# W5500_1_12.net
KiCad netlist of a schematic drawn in Altium Designer
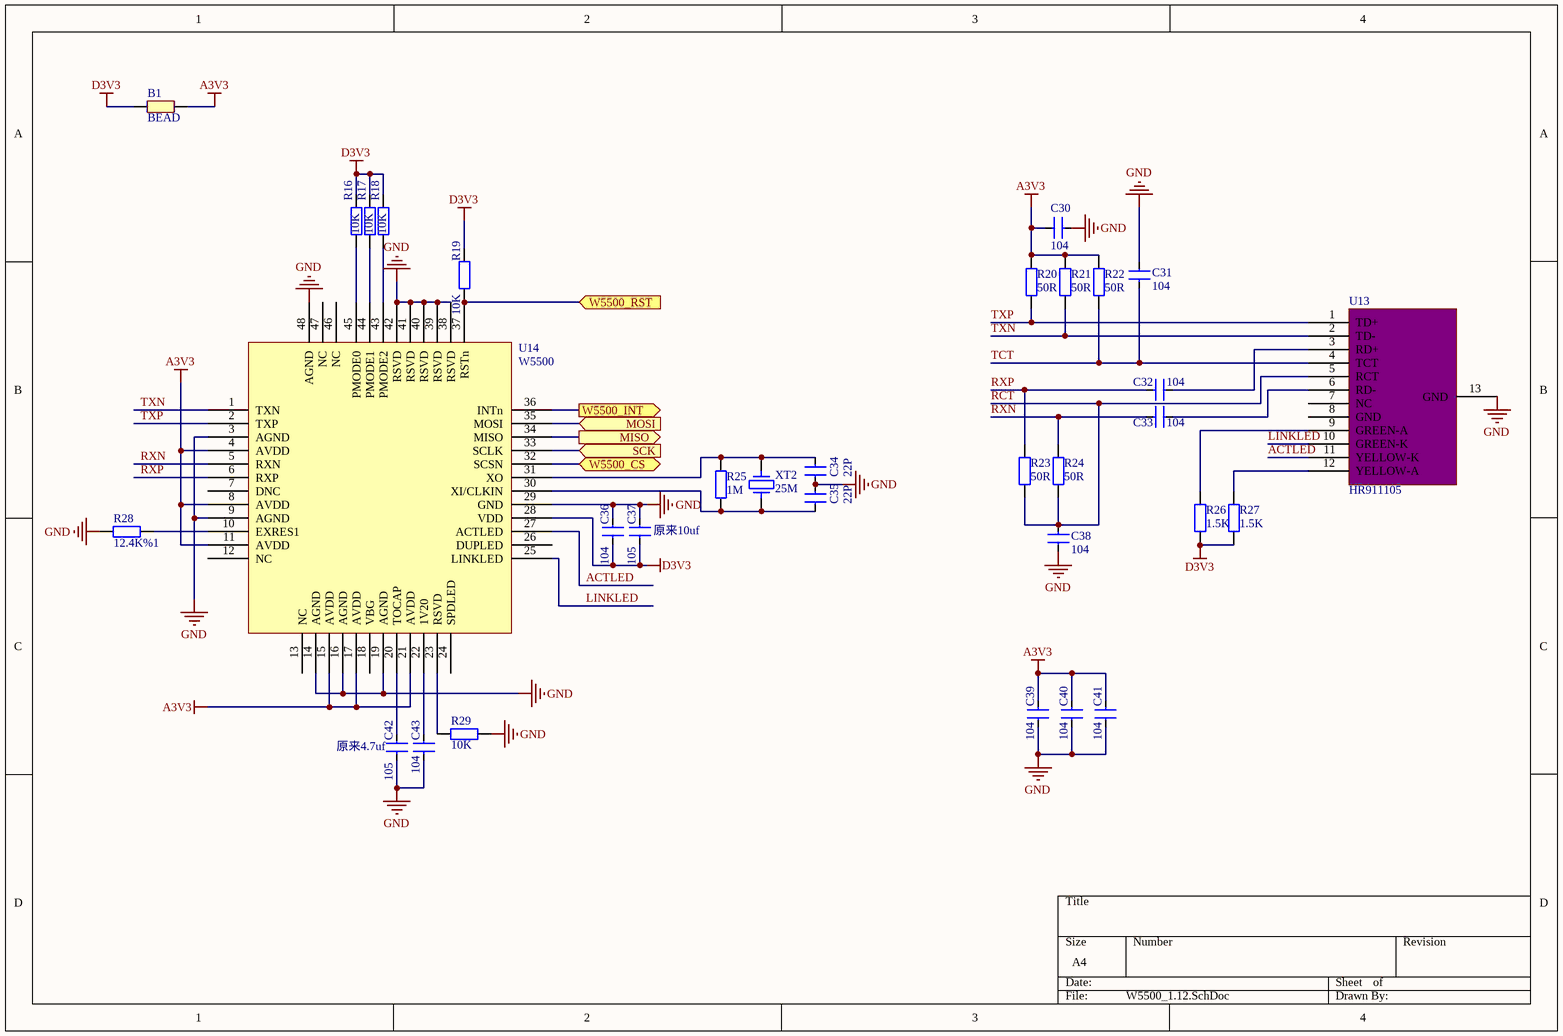
[diagram p0: W5500_1.12.SchDoc]

(export (version "E")
  (design (tool "Eeschema 10.0.6"))
  (components
    (comp (ref "B1")
      (value "BEAD")
      (footprint "0603L")
      (description "磁珠")
      (libsource (lib "lib_AD") (part "BEAD"))
    )
    (comp (ref "C30")
      (value "104")
      (footprint "0603C")
      (description "普通小电容")
      (libsource (lib "lib_AD") (part "CAP"))
    )
    (comp (ref "C31")
      (value "104")
      (footprint "0603C")
      (description "普通小电容")
      (libsource (lib "lib_AD") (part "CAP"))
    )
    (comp (ref "C32")
      (value "104")
      (footprint "0603C")
      (description "普通小电容")
      (libsource (lib "lib_AD") (part "CAP"))
    )
    (comp (ref "C33")
      (value "104")
      (footprint "0603C")
      (description "普通小电容")
      (libsource (lib "lib_AD") (part "CAP"))
    )
    (comp (ref "C34")
      (value "22P")
      (footprint "0603C")
      (description "普通小电容")
      (libsource (lib "lib_AD") (part "CAP"))
    )
    (comp (ref "C35")
      (value "22P")
      (footprint "0603C")
      (description "普通小电容")
      (libsource (lib "lib_AD") (part "CAP"))
    )
    (comp (ref "C36")
      (value "104")
      (footprint "0603C")
      (description "普通小电容")
      (libsource (lib "lib_AD") (part "CAP"))
    )
    (comp (ref "C37")
      (value "105")
      (footprint "0603C")
      (description "普通小电容")
      (libsource (lib "lib_AD") (part "CAP"))
    )
    (comp (ref "C38")
      (value "104")
      (footprint "0603C")
      (description "普通小电容")
      (libsource (lib "lib_AD") (part "CAP"))
    )
    (comp (ref "C39")
      (value "104")
      (footprint "0603C")
      (description "普通小电容")
      (libsource (lib "lib_AD") (part "CAP"))
    )
    (comp (ref "C40")
      (value "104")
      (footprint "0603C")
      (description "普通小电容")
      (libsource (lib "lib_AD") (part "CAP"))
    )
    (comp (ref "C41")
      (value "104")
      (footprint "0603C")
      (description "普通小电容")
      (libsource (lib "lib_AD") (part "CAP"))
    )
    (comp (ref "C42")
      (value "105")
      (footprint "0603C")
      (description "普通小电容")
      (libsource (lib "lib_AD") (part "CAP"))
    )
    (comp (ref "C43")
      (value "104")
      (footprint "0603C")
      (description "普通小电容")
      (libsource (lib "lib_AD") (part "CAP"))
    )
    (comp (ref "R16")
      (value "10K")
      (footprint "0603R")
      (description "普通电阻")
      (libsource (lib "lib_AD") (part "RES"))
    )
    (comp (ref "R17")
      (value "10K")
      (footprint "0603R")
      (description "普通电阻")
      (libsource (lib "lib_AD") (part "RES"))
    )
    (comp (ref "R18")
      (value "10K")
      (footprint "0603R")
      (description "普通电阻")
      (libsource (lib "lib_AD") (part "RES"))
    )
    (comp (ref "R19")
      (value "10K")
      (footprint "0603R")
      (description "普通电阻")
      (libsource (lib "lib_AD") (part "RES"))
    )
    (comp (ref "R20")
      (value "50R")
      (footprint "0603R")
      (description "普通电阻")
      (libsource (lib "lib_AD") (part "RES"))
    )
    (comp (ref "R21")
      (value "50R")
      (footprint "0603R")
      (description "普通电阻")
      (libsource (lib "lib_AD") (part "RES"))
    )
    (comp (ref "R22")
      (value "50R")
      (footprint "0603R")
      (description "普通电阻")
      (libsource (lib "lib_AD") (part "RES"))
    )
    (comp (ref "R23")
      (value "50R")
      (footprint "0603R")
      (description "普通电阻")
      (libsource (lib "") (part "RES_2"))
    )
    (comp (ref "R24")
      (value "50R")
      (footprint "0603R")
      (description "普通电阻")
      (libsource (lib "") (part "RES_2"))
    )
    (comp (ref "R25")
      (value "1M")
      (footprint "0603R")
      (description "普通电阻")
      (libsource (lib "lib_AD") (part "RES"))
    )
    (comp (ref "R26")
      (value "1.5K")
      (footprint "0603R")
      (description "普通电阻")
      (libsource (lib "lib_AD") (part "RES"))
    )
    (comp (ref "R27")
      (value "1.5K")
      (footprint "0603R")
      (description "普通电阻")
      (libsource (lib "lib_AD") (part "RES"))
    )
    (comp (ref "R28")
      (value "12.4K%1")
      (footprint "0603R")
      (description "普通电阻")
      (libsource (lib "") (part "RES_1"))
    )
    (comp (ref "R29")
      (value "10K")
      (footprint "0603R")
      (description "普通电阻")
      (libsource (lib "") (part "RES_1"))
    )
    (comp (ref "U13")
      (value "HR911105")
      (footprint "HR911105A")
      (libsource (lib "Connectors") (part "HR911105"))
    )
    (comp (ref "U14") (value "W5500") (footprint "LQFP48") (libsource (lib "IC") (part "W5500")))
    (comp (ref "XT2")
      (value "25M")
      (footprint "5032")
      (description "晶振")
      (libsource (lib "lib_AD") (part "XT"))
    )
  )
  (nets
    (net (code "1") (name "/ACTLED") (class "Default")
      (node (ref "U13") (pin "11") (pinfunction "YELLOW-K_11") (pintype "power_in"))
      (node (ref "U14") (pin "27") (pinfunction "ACTLED_27") (pintype "passive"))
    )
    (net (code "2") (name "/LINKLED") (class "Default")
      (node (ref "U13") (pin "10") (pinfunction "GREEN-K_10") (pintype "power_in"))
      (node (ref "U14") (pin "25") (pinfunction "LINKLED_25") (pintype "passive"))
    )
    (net (code "3") (name "/MISO") (class "Default")
      (node (ref "U14") (pin "34") (pinfunction "MISO_34") (pintype "passive"))
    )
    (net (code "4") (name "/MOSI") (class "Default")
      (node (ref "U14") (pin "35") (pinfunction "MOSI_35") (pintype "passive"))
    )
    (net (code "5") (name "/RCT") (class "Default")
      (node (ref "C38") (pin "1") (pinfunction "1_1") (pintype "passive"))
      (node (ref "R23") (pin "2") (pinfunction "2_2") (pintype "passive"))
      (node (ref "R24") (pin "2") (pinfunction "2_2") (pintype "passive"))
      (node (ref "U13") (pin "5") (pinfunction "RCT_5") (pintype "power_in"))
    )
    (net (code "6") (name "/RXN") (class "Default")
      (node (ref "C33") (pin "2") (pinfunction "2_2") (pintype "passive"))
      (node (ref "R24") (pin "1") (pinfunction "1_1") (pintype "passive"))
      (node (ref "U14") (pin "5") (pinfunction "RXN_5") (pintype "passive"))
    )
    (net (code "7") (name "/RXP") (class "Default")
      (node (ref "C32") (pin "2") (pinfunction "2_2") (pintype "passive"))
      (node (ref "R23") (pin "1") (pinfunction "1_1") (pintype "passive"))
      (node (ref "U14") (pin "6") (pinfunction "RXP_6") (pintype "passive"))
    )
    (net (code "8") (name "/SCK") (class "Default")
      (node (ref "U14") (pin "33") (pinfunction "SCLK_33") (pintype "passive"))
    )
    (net (code "9") (name "/TCT") (class "Default")
      (node (ref "C31") (pin "2") (pinfunction "2_2") (pintype "passive"))
      (node (ref "R22") (pin "1") (pinfunction "1_1") (pintype "passive"))
      (node (ref "U13") (pin "4") (pinfunction "TCT_4") (pintype "power_in"))
    )
    (net (code "10") (name "/TXN") (class "Default")
      (node (ref "R21") (pin "1") (pinfunction "1_1") (pintype "passive"))
      (node (ref "U13") (pin "2") (pinfunction "TD-_2") (pintype "power_in"))
      (node (ref "U14") (pin "1") (pinfunction "TXN_1") (pintype "passive"))
    )
    (net (code "11") (name "/TXP") (class "Default")
      (node (ref "R20") (pin "1") (pinfunction "1_1") (pintype "passive"))
      (node (ref "U13") (pin "1") (pinfunction "TD+_1") (pintype "power_in"))
      (node (ref "U14") (pin "2") (pinfunction "TXP_2") (pintype "passive"))
    )
    (net (code "12") (name "/W5500_CS") (class "Default")
      (node (ref "U14") (pin "32") (pinfunction "SCSN_32") (pintype "passive"))
    )
    (net (code "13") (name "/W5500_INT") (class "Default")
      (node (ref "U14") (pin "36") (pinfunction "INTn_36") (pintype "passive"))
    )
    (net (code "14") (name "/W5500_RST") (class "Default")
      (node (ref "R19") (pin "1") (pinfunction "1_1") (pintype "passive"))
      (node (ref "U14") (pin "37") (pinfunction "RSTn_37") (pintype "passive"))
    )
    (net (code "15") (name "A3V3") (class "Default")
      (node (ref "B1") (pin "2") (pinfunction "2_2") (pintype "passive"))
      (node (ref "C30") (pin "1") (pinfunction "1_1") (pintype "passive"))
      (node (ref "C39") (pin "2") (pinfunction "2_2") (pintype "passive"))
      (node (ref "C40") (pin "2") (pinfunction "2_2") (pintype "passive"))
      (node (ref "C41") (pin "2") (pinfunction "2_2") (pintype "passive"))
      (node (ref "R20") (pin "2") (pinfunction "2_2") (pintype "passive"))
      (node (ref "R21") (pin "2") (pinfunction "2_2") (pintype "passive"))
      (node (ref "R22") (pin "2") (pinfunction "2_2") (pintype "passive"))
      (node (ref "U14") (pin "11") (pinfunction "AVDD_11") (pintype "passive"))
      (node (ref "U14") (pin "15") (pinfunction "AVDD_15") (pintype "passive"))
      (node (ref "U14") (pin "17") (pinfunction "AVDD_17") (pintype "passive"))
      (node (ref "U14") (pin "21") (pinfunction "AVDD_21") (pintype "passive"))
      (node (ref "U14") (pin "4") (pinfunction "AVDD_4") (pintype "passive"))
      (node (ref "U14") (pin "8") (pinfunction "AVDD_8") (pintype "passive"))
    )
    (net (code "16") (name "D3V3") (class "Default")
      (node (ref "B1") (pin "1") (pinfunction "1_1") (pintype "passive"))
      (node (ref "C36") (pin "1") (pinfunction "1_1") (pintype "passive"))
      (node (ref "C37") (pin "1") (pinfunction "1_1") (pintype "passive"))
      (node (ref "R16") (pin "2") (pinfunction "2_2") (pintype "passive"))
      (node (ref "R17") (pin "2") (pinfunction "2_2") (pintype "passive"))
      (node (ref "R18") (pin "2") (pinfunction "2_2") (pintype "passive"))
      (node (ref "R19") (pin "2") (pinfunction "2_2") (pintype "passive"))
      (node (ref "R26") (pin "1") (pinfunction "1_1") (pintype "passive"))
      (node (ref "R27") (pin "1") (pinfunction "1_1") (pintype "passive"))
      (node (ref "U14") (pin "28") (pinfunction "VDD_28") (pintype "passive"))
    )
    (net (code "17") (name "GND") (class "Default")
      (node (ref "C30") (pin "2") (pinfunction "2_2") (pintype "passive"))
      (node (ref "C31") (pin "1") (pinfunction "1_1") (pintype "passive"))
      (node (ref "C34") (pin "1") (pinfunction "1_1") (pintype "passive"))
      (node (ref "C35") (pin "2") (pinfunction "2_2") (pintype "passive"))
      (node (ref "C36") (pin "2") (pinfunction "2_2") (pintype "passive"))
      (node (ref "C37") (pin "2") (pinfunction "2_2") (pintype "passive"))
      (node (ref "C38") (pin "2") (pinfunction "2_2") (pintype "passive"))
      (node (ref "C39") (pin "1") (pinfunction "1_1") (pintype "passive"))
      (node (ref "C40") (pin "1") (pinfunction "1_1") (pintype "passive"))
      (node (ref "C41") (pin "1") (pinfunction "1_1") (pintype "passive"))
      (node (ref "C42") (pin "1") (pinfunction "1_1") (pintype "passive"))
      (node (ref "C43") (pin "1") (pinfunction "1_1") (pintype "passive"))
      (node (ref "R28") (pin "2") (pinfunction "2_2") (pintype "passive"))
      (node (ref "R29") (pin "1") (pinfunction "1_1") (pintype "passive"))
      (node (ref "U13") (pin "13") (pinfunction "GND_13") (pintype "passive"))
      (node (ref "U14") (pin "14") (pinfunction "AGND_14") (pintype "passive"))
      (node (ref "U14") (pin "16") (pinfunction "AGND_16") (pintype "passive"))
      (node (ref "U14") (pin "19") (pinfunction "AGND_19") (pintype "passive"))
      (node (ref "U14") (pin "29") (pinfunction "GND_29") (pintype "passive"))
      (node (ref "U14") (pin "3") (pinfunction "AGND_3") (pintype "passive"))
      (node (ref "U14") (pin "38") (pinfunction "RSVD_38") (pintype "passive"))
      (node (ref "U14") (pin "39") (pinfunction "RSVD_39") (pintype "passive"))
      (node (ref "U14") (pin "40") (pinfunction "RSVD_40") (pintype "passive"))
      (node (ref "U14") (pin "41") (pinfunction "RSVD_41") (pintype "passive"))
      (node (ref "U14") (pin "42") (pinfunction "RSVD_42") (pintype "passive"))
      (node (ref "U14") (pin "48") (pinfunction "AGND_48") (pintype "passive"))
      (node (ref "U14") (pin "9") (pinfunction "AGND_9") (pintype "passive"))
    )
    (net (code "18") (name "Net-(R29-Pad2)") (class "Default")
      (node (ref "R29") (pin "2") (pinfunction "2_2") (pintype "passive"))
      (node (ref "U14") (pin "23") (pinfunction "RSVD_23") (pintype "passive"))
    )
    (net (code "19") (name "Net-(U13-GREEN-A)") (class "Default")
      (node (ref "R26") (pin "2") (pinfunction "2_2") (pintype "passive"))
      (node (ref "U13") (pin "9") (pinfunction "GREEN-A_9") (pintype "power_in"))
    )
    (net (code "20") (name "Net-(U13-RD+)") (class "Default")
      (node (ref "C32") (pin "1") (pinfunction "1_1") (pintype "passive"))
      (node (ref "U13") (pin "3") (pinfunction "RD+_3") (pintype "power_in"))
    )
    (net (code "21") (name "Net-(U13-RD-)") (class "Default")
      (node (ref "C33") (pin "1") (pinfunction "1_1") (pintype "passive"))
      (node (ref "U13") (pin "6") (pinfunction "RD-_6") (pintype "power_in"))
    )
    (net (code "22") (name "Net-(U13-YELLOW-A)") (class "Default")
      (node (ref "R27") (pin "2") (pinfunction "2_2") (pintype "passive"))
      (node (ref "U13") (pin "12") (pinfunction "YELLOW-A_12") (pintype "power_in"))
    )
    (net (code "23") (name "Net-(U14-1V20)") (class "Default")
      (node (ref "C43") (pin "2") (pinfunction "2_2") (pintype "passive"))
      (node (ref "U14") (pin "22") (pinfunction "1V20_22") (pintype "passive"))
    )
    (net (code "24") (name "Net-(U14-EXRES1)") (class "Default")
      (node (ref "R28") (pin "1") (pinfunction "1_1") (pintype "passive"))
      (node (ref "U14") (pin "10") (pinfunction "EXRES1_10") (pintype "passive"))
    )
    (net (code "25") (name "Net-(U14-PMODE0)") (class "Default")
      (node (ref "R16") (pin "1") (pinfunction "1_1") (pintype "passive"))
      (node (ref "U14") (pin "45") (pinfunction "PMODE0_45") (pintype "passive"))
    )
    (net (code "26") (name "Net-(U14-PMODE1)") (class "Default")
      (node (ref "R17") (pin "1") (pinfunction "1_1") (pintype "passive"))
      (node (ref "U14") (pin "44") (pinfunction "PMODE1_44") (pintype "passive"))
    )
    (net (code "27") (name "Net-(U14-PMODE2)") (class "Default")
      (node (ref "R18") (pin "1") (pinfunction "1_1") (pintype "passive"))
      (node (ref "U14") (pin "43") (pinfunction "PMODE2_43") (pintype "passive"))
    )
    (net (code "28") (name "Net-(U14-TOCAP)") (class "Default")
      (node (ref "C42") (pin "2") (pinfunction "2_2") (pintype "passive"))
      (node (ref "U14") (pin "20") (pinfunction "TOCAP_20") (pintype "passive"))
    )
    (net (code "29") (name "Net-(U14-XI{slash}CLKIN)") (class "Default")
      (node (ref "C35") (pin "1") (pinfunction "1_1") (pintype "passive"))
      (node (ref "R25") (pin "1") (pinfunction "1_1") (pintype "passive"))
      (node (ref "U14") (pin "30") (pinfunction "XI/CLKIN_30") (pintype "passive"))
      (node (ref "XT2") (pin "1") (pinfunction "1_1") (pintype "passive"))
    )
    (net (code "30") (name "Net-(U14-XO)") (class "Default")
      (node (ref "C34") (pin "2") (pinfunction "2_2") (pintype "passive"))
      (node (ref "R25") (pin "2") (pinfunction "2_2") (pintype "passive"))
      (node (ref "U14") (pin "31") (pinfunction "XO_31") (pintype "passive"))
      (node (ref "XT2") (pin "2") (pinfunction "2_2") (pintype "passive"))
    )
    (net (code "31") (name "unconnected-(U13-GND-Pad8)") (class "Default")
      (node (ref "U13") (pin "8") (pinfunction "GND_8") (pintype "power_in"))
    )
    (net (code "32") (name "unconnected-(U13-NC-Pad7)") (class "Default")
      (node (ref "U13") (pin "7") (pinfunction "NC_7") (pintype "power_in"))
    )
    (net (code "33") (name "unconnected-(U14-DNC-Pad7)") (class "Default")
      (node (ref "U14") (pin "7") (pinfunction "DNC_7") (pintype "passive"))
    )
    (net (code "34") (name "unconnected-(U14-DUPLED-Pad26)") (class "Default")
      (node (ref "U14") (pin "26") (pinfunction "DUPLED_26") (pintype "passive"))
    )
    (net (code "35") (name "unconnected-(U14-NC-Pad12)") (class "Default")
      (node (ref "U14") (pin "12") (pinfunction "NC_12") (pintype "passive"))
    )
    (net (code "36") (name "unconnected-(U14-NC-Pad13)") (class "Default")
      (node (ref "U14") (pin "13") (pinfunction "NC_13") (pintype "passive"))
    )
    (net (code "37") (name "unconnected-(U14-NC-Pad46)") (class "Default")
      (node (ref "U14") (pin "46") (pinfunction "NC_46") (pintype "passive"))
    )
    (net (code "38") (name "unconnected-(U14-NC-Pad47)") (class "Default")
      (node (ref "U14") (pin "47") (pinfunction "NC_47") (pintype "passive"))
    )
    (net (code "39") (name "unconnected-(U14-SPDLED-Pad24)") (class "Default")
      (node (ref "U14") (pin "24") (pinfunction "SPDLED_24") (pintype "passive"))
    )
    (net (code "40") (name "unconnected-(U14-VBG-Pad18)") (class "Default")
      (node (ref "U14") (pin "18") (pinfunction "VBG_18") (pintype "passive"))
    )
  )
)
